# Main.net
KiCad netlist of a schematic drawn in Altium Designer
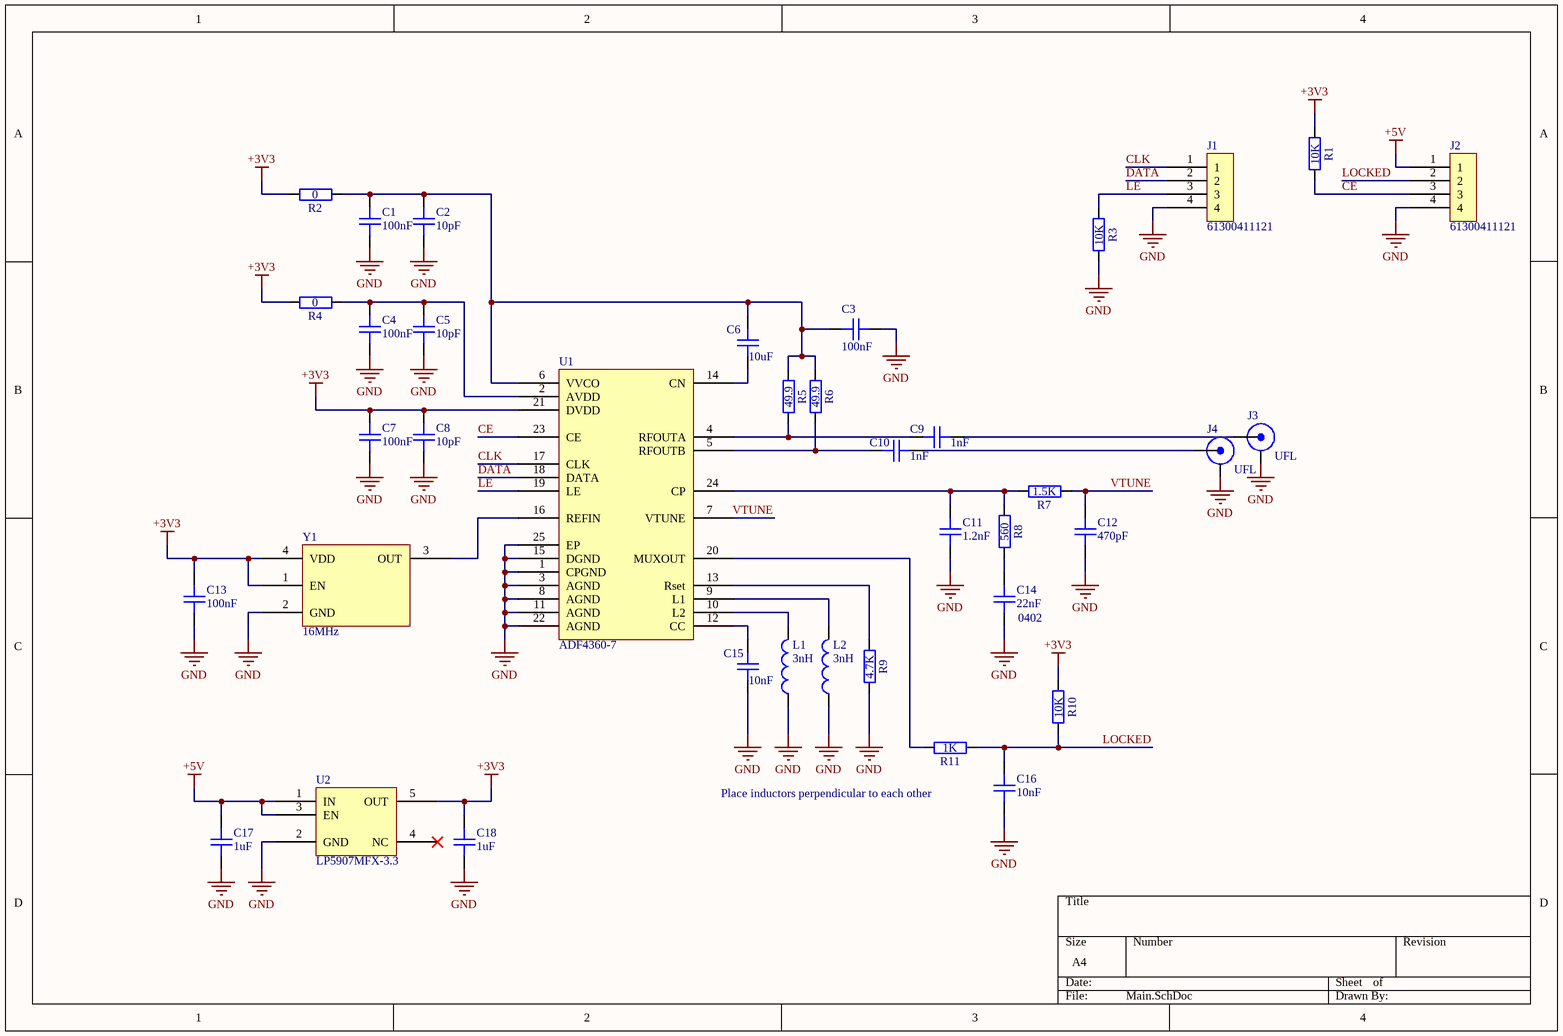
[diagram p0: Main.SchDoc]

(export (version "E")
  (design (tool "Eeschema 10.0.6"))
  (components
    (comp (ref "C1")
      (value "100nF")
      (footprint "GEN_C_0402")
      (fields (field (name "Comment") "CAP 100nF 16V X7R 0402"))
      (libsource (lib "DSO") (part "CAP 100nF 16V X7R 0402"))
    )
    (comp (ref "C2")
      (value "10pF")
      (footprint "GEN_C_0402")
      (libsource (lib "DSO") (part "CAP 10pF 50V C0G 0402"))
    )
    (comp (ref "C3")
      (value "100nF")
      (footprint "GEN_C_0402")
      (fields (field (name "Comment") "CAP 100nF 16V X7R 0402"))
      (libsource (lib "DSO") (part "CAP 100nF 16V X7R 0402"))
    )
    (comp (ref "C4")
      (value "100nF")
      (footprint "GEN_C_0402")
      (fields (field (name "Comment") "CAP 100nF 16V X7R 0402"))
      (libsource (lib "DSO") (part "CAP 100nF 16V X7R 0402"))
    )
    (comp (ref "C5")
      (value "10pF")
      (footprint "GEN_C_0402")
      (libsource (lib "DSO") (part "CAP 10pF 50V C0G 0402"))
    )
    (comp (ref "C6")
      (value "10uF")
      (footprint "GEN_C_0603")
      (fields (field (name "Comment") "CAP 10uF 10V X5R 0603"))
      (libsource (lib "DSO") (part "CAP 10uF 10V X5R 0603"))
    )
    (comp (ref "C7")
      (value "100nF")
      (footprint "GEN_C_0402")
      (fields (field (name "Comment") "CAP 100nF 16V X7R 0402"))
      (libsource (lib "DSO") (part "CAP 100nF 16V X7R 0402"))
    )
    (comp (ref "C8")
      (value "10pF")
      (footprint "GEN_C_0402")
      (libsource (lib "DSO") (part "CAP 10pF 50V C0G 0402"))
    )
    (comp (ref "C9")
      (value "1nF")
      (footprint "GEN_C_0402")
      (fields (field (name "Comment") "CAP 1nF 50V X7R 0402"))
      (libsource (lib "DSO") (part "CAP 1nF 50V X7R 0402"))
    )
    (comp (ref "C10")
      (value "1nF")
      (footprint "GEN_C_0402")
      (fields (field (name "Comment") "CAP 1nF 50V X7R 0402"))
      (libsource (lib "DSO") (part "CAP 1nF 50V X7R 0402"))
    )
    (comp (ref "C11")
      (value "1.2nF")
      (footprint "GEN_C_0603")
      (libsource (lib "DSO") (part "CAP 1.2nF 50V C0G 0603"))
    )
    (comp (ref "C12")
      (value "470pF")
      (footprint "GEN_C_0402")
      (libsource (lib "DSO") (part "CAP 470pF 50V C0G 0402"))
    )
    (comp (ref "C13")
      (value "100nF")
      (footprint "GEN_C_0402")
      (fields (field (name "Comment") "CAP 100nF 16V X7R 0402"))
      (libsource (lib "DSO") (part "CAP 100nF 16V X7R 0402"))
    )
    (comp (ref "C14")
      (value "22nF")
      (footprint "GEN_C_0402")
      (fields (field (name "PACKAGE") "0402") (field (name "Comment") "CAP 22nF 25V X7R 0402"))
      (libsource (lib "DSO") (part "CAP 22nF 25V X7R 0402"))
    )
    (comp (ref "C15")
      (value "10nF")
      (footprint "GEN_C_0402")
      (fields (field (name "Comment") "CAP 10nF 50V X7R 0402"))
      (libsource (lib "DSO") (part "CAP 10nF 50V X7R 0402"))
    )
    (comp (ref "C16")
      (value "10nF")
      (footprint "GEN_C_0402")
      (fields (field (name "Comment") "CAP 10nF 50V X7R 0402"))
      (libsource (lib "DSO") (part "CAP 10nF 50V X7R 0402"))
    )
    (comp (ref "C17")
      (value "1uF")
      (footprint "GEN_C_0402")
      (fields (field (name "Comment") "CAP 1uF 25V X5R 0402"))
      (libsource (lib "DSO") (part "CAP 1uF 25V X5R 0402"))
    )
    (comp (ref "C18")
      (value "1uF")
      (footprint "GEN_C_0402")
      (fields (field (name "Comment") "CAP 1uF 25V X5R 0402"))
      (libsource (lib "DSO") (part "CAP 1uF 25V X5R 0402"))
    )
    (comp (ref "J1")
      (value "61300411121")
      (footprint "GEN_2.54mm_4_Pin_TH")
      (libsource (lib "DSO") (part "CONN 2.54mm 4 Pin TH"))
    )
    (comp (ref "J2")
      (value "61300411121")
      (footprint "GEN_2.54mm_4_Pin_TH")
      (libsource (lib "DSO") (part "CONN 2.54mm 4 Pin TH"))
    )
    (comp (ref "J3") (value "UFL") (footprint "AMP_A-1JB") (libsource (lib "DSO") (part "UFL Jack SMD")))
    (comp (ref "J4") (value "UFL") (footprint "AMP_A-1JB") (libsource (lib "DSO") (part "UFL Jack SMD")))
    (comp (ref "L1")
      (value "3nH")
      (footprint "GEN_L_0402")
      (libsource (lib "DSO") (part "IND 3nH +/-0.05nH 0402"))
    )
    (comp (ref "L2")
      (value "3nH")
      (footprint "GEN_L_0402")
      (libsource (lib "DSO") (part "IND 3nH +/-0.05nH 0402"))
    )
    (comp (ref "R1")
      (value "10K")
      (footprint "GEN_R_0402")
      (fields (field (name "TOLERANCE") "1%") (field (name "Comment") "RES 10K OHM 1% 1/10W 0402"))
      (libsource (lib "DSO") (part "RES 10K OHM 1% 1/10W 0402"))
    )
    (comp (ref "R2")
      (value "0")
      (footprint "GEN_R_0402")
      (libsource (lib "DSO") (part "RES 0 OHM 1/16W 0402"))
    )
    (comp (ref "R3")
      (value "10K")
      (footprint "GEN_R_0402")
      (fields (field (name "TOLERANCE") "1%") (field (name "Comment") "RES 10K OHM 1% 1/10W 0402"))
      (libsource (lib "DSO") (part "RES 10K OHM 1% 1/10W 0402"))
    )
    (comp (ref "R4")
      (value "0")
      (footprint "GEN_R_0402")
      (libsource (lib "DSO") (part "RES 0 OHM 1/16W 0402"))
    )
    (comp (ref "R5")
      (value "49.9")
      (footprint "GEN_R_0402")
      (fields (field (name "TOLERANCE") "1%"))
      (libsource (lib "DSO") (part "RES 49.9 OHM 1% 1/10W 0402"))
    )
    (comp (ref "R6")
      (value "49.9")
      (footprint "GEN_R_0402")
      (fields (field (name "TOLERANCE") "1%"))
      (libsource (lib "DSO") (part "RES 49.9 OHM 1% 1/10W 0402"))
    )
    (comp (ref "R7")
      (value "1.5K")
      (footprint "GEN_R_0402")
      (fields (field (name "TOLERANCE") "1%"))
      (libsource (lib "DSO") (part "RES 1.5K OHM 1% 1/16W 0402"))
    )
    (comp (ref "R8")
      (value "560")
      (footprint "GEN_R_0402")
      (fields (field (name "TOLERANCE") "1%"))
      (libsource (lib "DSO") (part "RES 560 OHM 1% 1/16W 0402"))
    )
    (comp (ref "R9")
      (value "4.7K")
      (footprint "GEN_R_0402")
      (fields (field (name "TOLERANCE") "1%") (field (name "Comment") "RES 4.7K OHM 1% 1/10W 0402"))
      (libsource (lib "DSO") (part "RES 4.7K OHM 1% 1/10W 0402"))
    )
    (comp (ref "R10")
      (value "10K")
      (footprint "GEN_R_0402")
      (fields (field (name "TOLERANCE") "1%") (field (name "Comment") "RES 10K OHM 1% 1/10W 0402"))
      (libsource (lib "DSO") (part "RES 10K OHM 1% 1/10W 0402"))
    )
    (comp (ref "R11")
      (value "1K")
      (footprint "GEN_R_0402")
      (fields (field (name "TOLERANCE") "1%") (field (name "Comment") "RES 1K OHM 1% 1/10W 0402"))
      (libsource (lib "DSO") (part "RES 1K OHM 1% 1/10W 0402"))
    )
    (comp (ref "U1")
      (value "ADF4360-7")
      (footprint "AD_QFN24_CP-24-14")
      (libsource (lib "DSO") (part "IC PLL ADF4360-7"))
    )
    (comp (ref "U2")
      (value "LP5907MFX-3.3")
      (footprint "GEN_SOT23_5_950_2900X1600X1450")
      (libsource (lib "DSO") (part "IC LDO LP5907MFX-3.3"))
    )
    (comp (ref "Y1")
      (value "16MHz")
      (footprint "ECS_TXO-2016")
      (libsource (lib "DSO") (part "OSC 16MHz ECS-TXO-2016"))
    )
  )
  (nets
    (net (code "1") (name "+3V3") (class "Default")
      (node (ref "C13") (pin "1") (pinfunction "1_1") (pintype "passive"))
      (node (ref "C18") (pin "2") (pinfunction "2_2") (pintype "passive"))
      (node (ref "C7") (pin "2") (pinfunction "2_2") (pintype "passive"))
      (node (ref "C8") (pin "2") (pinfunction "2_2") (pintype "passive"))
      (node (ref "R1") (pin "1") (pinfunction "1_1") (pintype "passive"))
      (node (ref "R10") (pin "1") (pinfunction "1_1") (pintype "passive"))
      (node (ref "R2") (pin "1") (pinfunction "1_1") (pintype "passive"))
      (node (ref "R4") (pin "1") (pinfunction "1_1") (pintype "passive"))
      (node (ref "U1") (pin "21") (pinfunction "DVDD_21") (pintype "passive"))
      (node (ref "U2") (pin "5") (pinfunction "OUT_5") (pintype "power_in"))
      (node (ref "Y1") (pin "1") (pinfunction "EN_1") (pintype "passive"))
      (node (ref "Y1") (pin "4") (pinfunction "VDD_4") (pintype "power_in"))
    )
    (net (code "2") (name "+5V") (class "Default")
      (node (ref "C17") (pin "2") (pinfunction "2_2") (pintype "passive"))
      (node (ref "J2") (pin "1") (pinfunction "1_1") (pintype "passive"))
      (node (ref "U2") (pin "1") (pinfunction "IN_1") (pintype "power_in"))
      (node (ref "U2") (pin "3") (pinfunction "EN_3") (pintype "passive"))
    )
    (net (code "3") (name "/CE") (class "Default")
      (node (ref "J2") (pin "3") (pinfunction "3_3") (pintype "passive"))
      (node (ref "R1") (pin "2") (pinfunction "2_2") (pintype "passive"))
      (node (ref "U1") (pin "23") (pinfunction "CE_23") (pintype "passive"))
    )
    (net (code "4") (name "/CLK") (class "Default")
      (node (ref "J1") (pin "1") (pinfunction "1_1") (pintype "passive"))
      (node (ref "U1") (pin "17") (pinfunction "CLK_17") (pintype "passive"))
    )
    (net (code "5") (name "/DATA") (class "Default")
      (node (ref "J1") (pin "2") (pinfunction "2_2") (pintype "passive"))
      (node (ref "U1") (pin "18") (pinfunction "DATA_18") (pintype "passive"))
    )
    (net (code "6") (name "/LE") (class "Default")
      (node (ref "J1") (pin "3") (pinfunction "3_3") (pintype "passive"))
      (node (ref "R3") (pin "1") (pinfunction "1_1") (pintype "passive"))
      (node (ref "U1") (pin "19") (pinfunction "LE_19") (pintype "passive"))
    )
    (net (code "7") (name "/LOCKED") (class "Default")
      (node (ref "C16") (pin "2") (pinfunction "2_2") (pintype "passive"))
      (node (ref "J2") (pin "2") (pinfunction "2_2") (pintype "passive"))
      (node (ref "R10") (pin "2") (pinfunction "2_2") (pintype "passive"))
      (node (ref "R11") (pin "2") (pinfunction "2_2") (pintype "passive"))
    )
    (net (code "8") (name "/VTUNE") (class "Default")
      (node (ref "C12") (pin "2") (pinfunction "2_2") (pintype "passive"))
      (node (ref "R7") (pin "2") (pinfunction "2_2") (pintype "passive"))
      (node (ref "U1") (pin "7") (pinfunction "VTUNE_7") (pintype "passive"))
    )
    (net (code "9") (name "GND") (class "Default")
      (node (ref "C1") (pin "1") (pinfunction "1_1") (pintype "passive"))
      (node (ref "C11") (pin "1") (pinfunction "1_1") (pintype "passive"))
      (node (ref "C12") (pin "1") (pinfunction "1_1") (pintype "passive"))
      (node (ref "C13") (pin "2") (pinfunction "2_2") (pintype "passive"))
      (node (ref "C14") (pin "1") (pinfunction "1_1") (pintype "passive"))
      (node (ref "C15") (pin "1") (pinfunction "1_1") (pintype "passive"))
      (node (ref "C16") (pin "1") (pinfunction "1_1") (pintype "passive"))
      (node (ref "C17") (pin "1") (pinfunction "1_1") (pintype "passive"))
      (node (ref "C18") (pin "1") (pinfunction "1_1") (pintype "passive"))
      (node (ref "C2") (pin "1") (pinfunction "1_1") (pintype "passive"))
      (node (ref "C3") (pin "1") (pinfunction "1_1") (pintype "passive"))
      (node (ref "C4") (pin "1") (pinfunction "1_1") (pintype "passive"))
      (node (ref "C5") (pin "1") (pinfunction "1_1") (pintype "passive"))
      (node (ref "C7") (pin "1") (pinfunction "1_1") (pintype "passive"))
      (node (ref "C8") (pin "1") (pinfunction "1_1") (pintype "passive"))
      (node (ref "J1") (pin "4") (pinfunction "4_4") (pintype "passive"))
      (node (ref "J2") (pin "4") (pinfunction "4_4") (pintype "passive"))
      (node (ref "J3") (pin "2") (pinfunction "SHIELD_2") (pintype "passive"))
      (node (ref "J4") (pin "2") (pinfunction "SHIELD_2") (pintype "passive"))
      (node (ref "L1") (pin "1") (pinfunction "1_1") (pintype "passive"))
      (node (ref "L2") (pin "1") (pinfunction "1_1") (pintype "passive"))
      (node (ref "R3") (pin "2") (pinfunction "2_2") (pintype "passive"))
      (node (ref "R9") (pin "1") (pinfunction "1_1") (pintype "passive"))
      (node (ref "U1") (pin "1") (pinfunction "CPGND_1") (pintype "power_in"))
      (node (ref "U1") (pin "11") (pinfunction "AGND_11") (pintype "passive"))
      (node (ref "U1") (pin "15") (pinfunction "DGND_15") (pintype "passive"))
      (node (ref "U1") (pin "22") (pinfunction "AGND_22") (pintype "passive"))
      (node (ref "U1") (pin "25") (pinfunction "EP_25") (pintype "passive"))
      (node (ref "U1") (pin "3") (pinfunction "AGND_3") (pintype "passive"))
      (node (ref "U1") (pin "8") (pinfunction "AGND_8") (pintype "passive"))
      (node (ref "U2") (pin "2") (pinfunction "GND_2") (pintype "power_in"))
      (node (ref "Y1") (pin "2") (pinfunction "GND_2") (pintype "power_in"))
    )
    (net (code "10") (name "Net-(C14-Pad2)") (class "Default")
      (node (ref "C14") (pin "2") (pinfunction "2_2") (pintype "passive"))
      (node (ref "R8") (pin "1") (pinfunction "1_1") (pintype "passive"))
    )
    (net (code "11") (name "Net-(J3-Signal)") (class "Default")
      (node (ref "C9") (pin "1") (pinfunction "1_1") (pintype "passive"))
      (node (ref "J3") (pin "1") (pinfunction "Signal_1") (pintype "passive"))
    )
    (net (code "12") (name "Net-(J4-Signal)") (class "Default")
      (node (ref "C10") (pin "1") (pinfunction "1_1") (pintype "passive"))
      (node (ref "J4") (pin "1") (pinfunction "Signal_1") (pintype "passive"))
    )
    (net (code "13") (name "Net-(U1-AVDD)") (class "Default")
      (node (ref "C4") (pin "2") (pinfunction "2_2") (pintype "passive"))
      (node (ref "C5") (pin "2") (pinfunction "2_2") (pintype "passive"))
      (node (ref "R4") (pin "2") (pinfunction "2_2") (pintype "passive"))
      (node (ref "U1") (pin "2") (pinfunction "AVDD_2") (pintype "passive"))
    )
    (net (code "14") (name "Net-(U1-CC)") (class "Default")
      (node (ref "C15") (pin "2") (pinfunction "2_2") (pintype "passive"))
      (node (ref "U1") (pin "12") (pinfunction "CC_12") (pintype "passive"))
    )
    (net (code "15") (name "Net-(U1-CN)") (class "Default")
      (node (ref "C6") (pin "1") (pinfunction "1_1") (pintype "passive"))
      (node (ref "U1") (pin "14") (pinfunction "CN_14") (pintype "passive"))
    )
    (net (code "16") (name "Net-(U1-CP)") (class "Default")
      (node (ref "C11") (pin "2") (pinfunction "2_2") (pintype "passive"))
      (node (ref "R7") (pin "1") (pinfunction "1_1") (pintype "passive"))
      (node (ref "R8") (pin "2") (pinfunction "2_2") (pintype "passive"))
      (node (ref "U1") (pin "24") (pinfunction "CP_24") (pintype "passive"))
    )
    (net (code "17") (name "Net-(U1-L1)") (class "Default")
      (node (ref "L2") (pin "2") (pinfunction "2_2") (pintype "passive"))
      (node (ref "U1") (pin "9") (pinfunction "L1_9") (pintype "passive"))
    )
    (net (code "18") (name "Net-(U1-L2)") (class "Default")
      (node (ref "L1") (pin "2") (pinfunction "2_2") (pintype "passive"))
      (node (ref "U1") (pin "10") (pinfunction "L2_10") (pintype "passive"))
    )
    (net (code "19") (name "Net-(U1-MUXOUT)") (class "Default")
      (node (ref "R11") (pin "1") (pinfunction "1_1") (pintype "passive"))
      (node (ref "U1") (pin "20") (pinfunction "MUXOUT_20") (pintype "passive"))
    )
    (net (code "20") (name "Net-(U1-REFIN)") (class "Default")
      (node (ref "U1") (pin "16") (pinfunction "REFIN_16") (pintype "passive"))
      (node (ref "Y1") (pin "3") (pinfunction "OUT_3") (pintype "passive"))
    )
    (net (code "21") (name "Net-(U1-RFOUTA)") (class "Default")
      (node (ref "C9") (pin "2") (pinfunction "2_2") (pintype "passive"))
      (node (ref "R5") (pin "1") (pinfunction "1_1") (pintype "passive"))
      (node (ref "U1") (pin "4") (pinfunction "RFOUTA_4") (pintype "passive"))
    )
    (net (code "22") (name "Net-(U1-RFOUTB)") (class "Default")
      (node (ref "C10") (pin "2") (pinfunction "2_2") (pintype "passive"))
      (node (ref "R6") (pin "1") (pinfunction "1_1") (pintype "passive"))
      (node (ref "U1") (pin "5") (pinfunction "RFOUTB_5") (pintype "passive"))
    )
    (net (code "23") (name "Net-(U1-Rset)") (class "Default")
      (node (ref "R9") (pin "2") (pinfunction "2_2") (pintype "passive"))
      (node (ref "U1") (pin "13") (pinfunction "Rset_13") (pintype "passive"))
    )
    (net (code "24") (name "Net-(U1-VVCO)") (class "Default")
      (node (ref "C1") (pin "2") (pinfunction "2_2") (pintype "passive"))
      (node (ref "C2") (pin "2") (pinfunction "2_2") (pintype "passive"))
      (node (ref "C3") (pin "2") (pinfunction "2_2") (pintype "passive"))
      (node (ref "C6") (pin "2") (pinfunction "2_2") (pintype "passive"))
      (node (ref "R2") (pin "2") (pinfunction "2_2") (pintype "passive"))
      (node (ref "R5") (pin "2") (pinfunction "2_2") (pintype "passive"))
      (node (ref "R6") (pin "2") (pinfunction "2_2") (pintype "passive"))
      (node (ref "U1") (pin "6") (pinfunction "VVCO_6") (pintype "passive"))
    )
    (net (code "25") (name "unconnected-(U2-NC-Pad4)") (class "Default")
      (node (ref "U2") (pin "4") (pinfunction "NC_4") (pintype "passive+no_connect"))
    )
  )
)
